# ESP8266Watch.net
KiCad netlist of a schematic drawn in Altium Designer
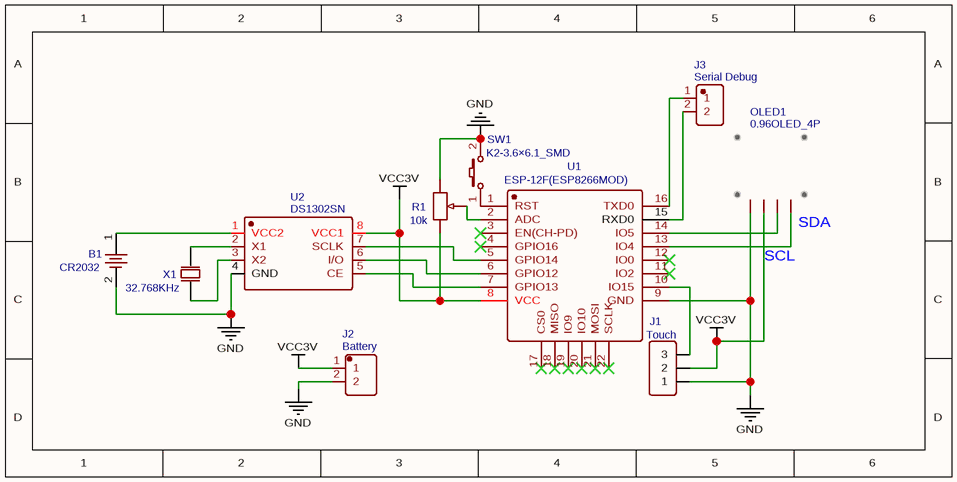
[diagram p0: ESP8266Watch.schdoc]

(export (version "E")
  (design (tool "Eeschema 10.0.6"))
  (components
    (comp (ref "B1")
      (value "CR2032")
      (fields (field (name "BOM_MANUFACTURER PART") "BS-2-1") (field (name "BOM_SUPPLIER PART") "C70376"))
      (libsource (lib "altium-import") (part "root_3_CR2032_"))
    )
    (comp (ref "J1")
      (value "Touch")
      (fields
        (field (name "BOM_SUPPLIER PART") "C146243")
        (field (name "BOM_MANUFACTURER PART") "Header-Female-2.54_1x3")
      )
      (libsource (lib "altium-import") (part "root_2_Touch_"))
    )
    (comp (ref "J2")
      (value "Battery")
      (fields (field (name "BOM_SUPPLIER PART") "C2324") (field (name "BOM_MANUFACTURER PART") "1.25T-1-2A"))
      (libsource (lib "altium-import") (part "root_0_Battery_"))
    )
    (comp (ref "J3")
      (value "Serial Debug")
      (fields
        (field (name "BOM_SUPPLIER PART") "C2879963")
        (field (name "BOM_MANUFACTURER PART") "A2005WV-2P")
        (field (name "CONTRIBUTOR") "LCSC")
      )
      (libsource (lib "altium-import") (part "root_0_Serial Debug_"))
    )
    (comp (ref "OLED1")
      (value "0.96OLED_4P")
      (fields (field (name "CONTRIBUTOR") "LCEDA_Lib"))
      (libsource (lib "altium-import") (part "root_0_0.96OLED_4P_"))
    )
    (comp (ref "R1")
      (value "10k")
      (fields (field (name "CONTRIBUTOR") "LCEDA_Lib"))
      (libsource (lib "altium-import") (part "root_3_10k_"))
    )
    (comp (ref "SW1")
      (value "K2-3.6×6.1_SMD")
      (fields
        (field (name "BOM_SUPPLIER PART") "C118141")
        (field (name "BOM_MANUFACTURER PART") "K2-1107ST-A4SW-06")
        (field (name "CONTRIBUTOR") "LCEDA_Lib")
      )
      (libsource (lib "altium-import") (part "root_1_K2-3.6×6.1_SMD_"))
    )
    (comp (ref "U1")
      (value "ESP-12F(ESP8266MOD)")
      (fields (field (name "BOM_SUPPLIER PART") "C82891"))
      (libsource (lib "altium-import") (part "root_0_ESP-12F(ESP8266MOD)_"))
    )
    (comp (ref "U2")
      (value "DS1302SN")
      (fields
        (field (name "BOM_MANUFACTURER PART") "DS1302SN+T&R")
        (field (name "BOM_SUPPLIER PART") "C41719")
      )
      (libsource (lib "altium-import") (part "root_0_DS1302SN_"))
    )
    (comp (ref "X1")
      (value "32.768KHz")
      (fields
        (field (name "BOM_SUPPLIER PART") "C100098")
        (field (name "BOM_MANUFACTURER PART") "CFS-20632768DZFB")
        (field (name "CONTRIBUTOR") "LCSC")
      )
      (libsource (lib "altium-import") (part "root_1_32.768KHz_"))
    )
  )
  (nets
    (net (code "1") (name "GND") (class "Default")
      (node (ref "B1") (pin "2") (pinfunction "2_2") (pintype "passive"))
      (node (ref "J1") (pin "1") (pinfunction "1_1") (pintype "passive"))
      (node (ref "J2") (pin "2") (pinfunction "2_2") (pintype "passive"))
      (node (ref "OLED1") (pin "1") (pinfunction "1_1") (pintype "passive"))
      (node (ref "R1") (pin "1") (pinfunction "1_1") (pintype "passive"))
      (node (ref "SW1") (pin "2") (pinfunction "2_2") (pintype "passive"))
      (node (ref "U1") (pin "9") (pinfunction "GND_9") (pintype "passive"))
      (node (ref "U2") (pin "4") (pinfunction "GND_4") (pintype "passive"))
    )
    (net (code "2") (name "Net-(U1-ADC)") (class "Default")
      (node (ref "R1") (pin "2") (pinfunction "2_2") (pintype "passive"))
      (node (ref "U1") (pin "2") (pinfunction "ADC_2") (pintype "passive"))
    )
    (net (code "3") (name "Net-(U1-GPIO12)") (class "Default")
      (node (ref "U1") (pin "6") (pinfunction "GPIO12_6") (pintype "passive"))
      (node (ref "U2") (pin "6") (pinfunction "I/O_6") (pintype "passive"))
    )
    (net (code "4") (name "Net-(U1-GPIO13)") (class "Default")
      (node (ref "U1") (pin "7") (pinfunction "GPIO13_7") (pintype "passive"))
      (node (ref "U2") (pin "5") (pinfunction "CE_5") (pintype "passive"))
    )
    (net (code "5") (name "Net-(U1-GPIO14)") (class "Default")
      (node (ref "U1") (pin "5") (pinfunction "GPIO14_5") (pintype "passive"))
      (node (ref "U2") (pin "7") (pinfunction "SCLK_7") (pintype "passive"))
    )
    (net (code "6") (name "Net-(U1-IO4)") (class "Default")
      (node (ref "OLED1") (pin "4") (pinfunction "4_4") (pintype "passive"))
      (node (ref "U1") (pin "13") (pinfunction "IO4_13") (pintype "passive"))
    )
    (net (code "7") (name "Net-(U1-IO5)") (class "Default")
      (node (ref "OLED1") (pin "3") (pinfunction "3_3") (pintype "passive"))
      (node (ref "U1") (pin "14") (pinfunction "IO5_14") (pintype "passive"))
    )
    (net (code "8") (name "Net-(U1-IO15)") (class "Default")
      (node (ref "J1") (pin "3") (pinfunction "3_3") (pintype "passive"))
      (node (ref "U1") (pin "10") (pinfunction "IO15_10") (pintype "passive"))
    )
    (net (code "9") (name "Net-(U1-RST)") (class "Default")
      (node (ref "SW1") (pin "1") (pinfunction "1_1") (pintype "passive"))
      (node (ref "U1") (pin "1") (pinfunction "RST_1") (pintype "passive"))
    )
    (net (code "10") (name "Net-(U1-RXD0)") (class "Default")
      (node (ref "J3") (pin "2") (pinfunction "2_2") (pintype "passive"))
      (node (ref "U1") (pin "15") (pinfunction "RXD0_15") (pintype "passive"))
    )
    (net (code "11") (name "Net-(U1-TXD0)") (class "Default")
      (node (ref "J3") (pin "1") (pinfunction "1_1") (pintype "passive"))
      (node (ref "U1") (pin "16") (pinfunction "TXD0_16") (pintype "passive"))
    )
    (net (code "12") (name "Net-(U2-VCC2)") (class "Default")
      (node (ref "B1") (pin "1") (pinfunction "1_1") (pintype "passive"))
      (node (ref "U2") (pin "1") (pinfunction "VCC2_1") (pintype "passive"))
    )
    (net (code "13") (name "Net-(U2-X1)") (class "Default")
      (node (ref "U2") (pin "2") (pinfunction "X1_2") (pintype "passive"))
      (node (ref "X1") (pin "2") (pinfunction "OSC2_2") (pintype "passive"))
    )
    (net (code "14") (name "Net-(U2-X2)") (class "Default")
      (node (ref "U2") (pin "3") (pinfunction "X2_3") (pintype "passive"))
      (node (ref "X1") (pin "1") (pinfunction "OSC1_1") (pintype "passive"))
    )
    (net (code "15") (name "VCC3V") (class "Default")
      (node (ref "J1") (pin "2") (pinfunction "2_2") (pintype "passive"))
      (node (ref "J2") (pin "1") (pinfunction "1_1") (pintype "passive"))
      (node (ref "OLED1") (pin "2") (pinfunction "2_2") (pintype "passive"))
      (node (ref "R1") (pin "3") (pinfunction "3_3") (pintype "passive"))
      (node (ref "U1") (pin "8") (pinfunction "VCC_8") (pintype "passive"))
      (node (ref "U2") (pin "8") (pinfunction "VCC1_8") (pintype "passive"))
    )
    (net (code "16") (name "unconnected-(U1-CS0-Pad17)") (class "Default")
      (node (ref "U1") (pin "17") (pinfunction "CS0_17") (pintype "passive+no_connect"))
    )
    (net (code "17") (name "unconnected-(U1-EN(CH-PD)-Pad3)") (class "Default")
      (node (ref "U1") (pin "3") (pinfunction "EN(CH-PD)_3") (pintype "passive+no_connect"))
    )
    (net (code "18") (name "unconnected-(U1-GPIO16-Pad4)") (class "Default")
      (node (ref "U1") (pin "4") (pinfunction "GPIO16_4") (pintype "passive+no_connect"))
    )
    (net (code "19") (name "unconnected-(U1-IO0-Pad12)") (class "Default")
      (node (ref "U1") (pin "12") (pinfunction "IO0_12") (pintype "passive+no_connect"))
    )
    (net (code "20") (name "unconnected-(U1-IO2-Pad11)") (class "Default")
      (node (ref "U1") (pin "11") (pinfunction "IO2_11") (pintype "passive+no_connect"))
    )
    (net (code "21") (name "unconnected-(U1-IO9-Pad19)") (class "Default")
      (node (ref "U1") (pin "19") (pinfunction "IO9_19") (pintype "passive+no_connect"))
    )
    (net (code "22") (name "unconnected-(U1-IO10-Pad20)") (class "Default")
      (node (ref "U1") (pin "20") (pinfunction "IO10_20") (pintype "passive+no_connect"))
    )
    (net (code "23") (name "unconnected-(U1-MISO-Pad18)") (class "Default")
      (node (ref "U1") (pin "18") (pinfunction "MISO_18") (pintype "passive+no_connect"))
    )
    (net (code "24") (name "unconnected-(U1-MOSI-Pad21)") (class "Default")
      (node (ref "U1") (pin "21") (pinfunction "MOSI_21") (pintype "passive+no_connect"))
    )
    (net (code "25") (name "unconnected-(U1-SCLK-Pad22)") (class "Default")
      (node (ref "U1") (pin "22") (pinfunction "SCLK_22") (pintype "passive+no_connect"))
    )
  )
)
